# ARS_Schematic.net
KiCad netlist of a schematic drawn in Altium Designer
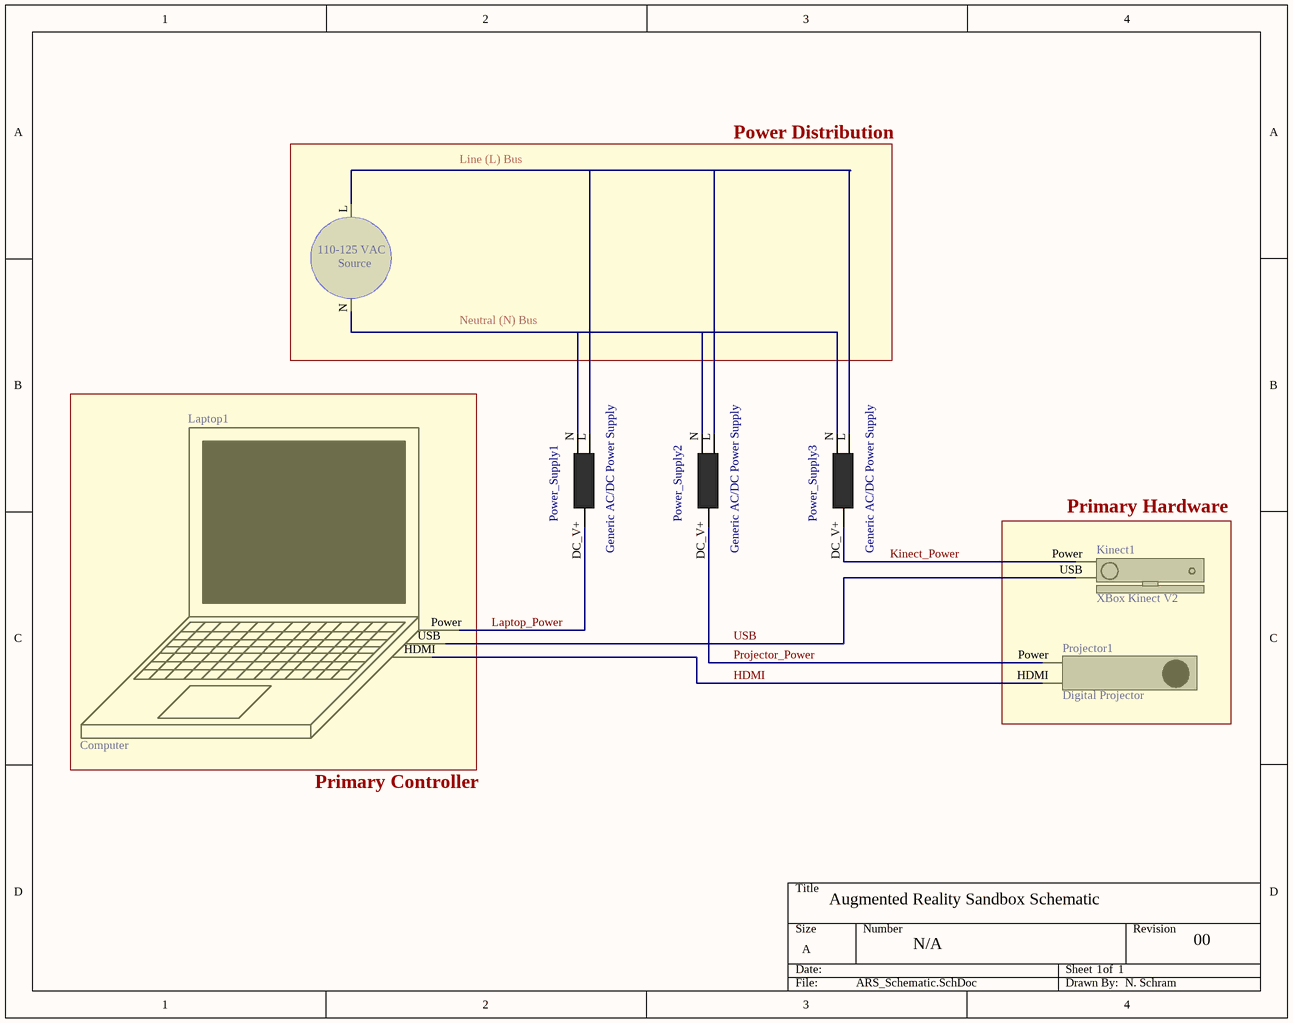
[diagram p0: ARS_Schematic.SchDoc]

(export (version "E")
  (design (tool "Eeschema 10.0.6"))
  (components
    (comp (ref "AC1")
      (value "110-125 VAC")
      (description "110-125 VAC SOURCE")
      (libsource (lib "ARS_Schematic_Library") (part "AC_Power_Source"))
    )
    (comp (ref "Kinect1")
      (value "XBox Kinect V2")
      (description "Microsoft XBox Kinect V2")
      (libsource (lib "ARS_Schematic_Library") (part "Xbox_Kinect_V2"))
    )
    (comp (ref "Laptop1")
      (value "Computer")
      (description "Laptop Computer")
      (libsource (lib "ARS_Schematic_Library") (part "Laptop"))
    )
    (comp (ref "Power_Supply1")
      (value "Generic AC/DC Power Supply")
      (libsource (lib "ARS_Schematic_Library") (part "Generic_Power_Supply"))
    )
    (comp (ref "Power_Supply2")
      (value "Generic AC/DC Power Supply")
      (libsource (lib "ARS_Schematic_Library") (part "Generic_Power_Supply"))
    )
    (comp (ref "Power_Supply3")
      (value "Generic AC/DC Power Supply")
      (libsource (lib "ARS_Schematic_Library") (part "Generic_Power_Supply"))
    )
    (comp (ref "Projector1")
      (value "Digital Projector")
      (description "BenQ Short Throw Digital Projector")
      (libsource (lib "ARS_Schematic_Library") (part "Digital_Projector"))
    )
  )
  (nets
    (net (code "1") (name "/HDMI") (class "Default")
      (node (ref "Laptop1") (pin "HDMI") (pinfunction "HDMI_HDMI") (pintype "passive"))
      (node (ref "Projector1") (pin "HDMI") (pinfunction "HDMI_HDMI") (pintype "passive"))
    )
    (net (code "2") (name "/Kinect_Power") (class "Default")
      (node (ref "Kinect1") (pin "Power") (pinfunction "Power_Power") (pintype "passive"))
      (node (ref "Power_Supply3") (pin "DC_V+") (pinfunction "DC_V+_DC_V+") (pintype "passive"))
    )
    (net (code "3") (name "/Laptop_Power") (class "Default")
      (node (ref "Laptop1") (pin "Power") (pinfunction "Power_Power") (pintype "passive"))
      (node (ref "Power_Supply1") (pin "DC_V+") (pinfunction "DC_V+_DC_V+") (pintype "passive"))
    )
    (net (code "6") (name "/Projector_Power") (class "Default")
      (node (ref "Power_Supply2") (pin "DC_V+") (pinfunction "DC_V+_DC_V+") (pintype "passive"))
      (node (ref "Projector1") (pin "Power") (pinfunction "Power_Power") (pintype "passive"))
    )
    (net (code "7") (name "/USB") (class "Default")
      (node (ref "Kinect1") (pin "USB") (pinfunction "USB_USB") (pintype "passive"))
      (node (ref "Laptop1") (pin "USB") (pinfunction "USB_USB") (pintype "passive"))
    )
    (net (code "8") (name "unconnected-(AC1-PadL)") (class "Default")
      (node (ref "AC1") (pin "L") (pinfunction "L_L") (pintype "passive"))
    )
    (net (code "9") (name "unconnected-(AC1-PadN)") (class "Default")
      (node (ref "AC1") (pin "N") (pinfunction "N_N") (pintype "passive"))
    )
    (net (code "10") (name "unconnected-(Power_Supply1-PadL)") (class "Default")
      (node (ref "Power_Supply1") (pin "L") (pinfunction "L_L") (pintype "passive"))
    )
    (net (code "11") (name "unconnected-(Power_Supply1-PadN)") (class "Default")
      (node (ref "Power_Supply1") (pin "N") (pinfunction "N_N") (pintype "passive"))
    )
    (net (code "12") (name "unconnected-(Power_Supply2-PadL)") (class "Default")
      (node (ref "Power_Supply2") (pin "L") (pinfunction "L_L") (pintype "passive"))
    )
    (net (code "13") (name "unconnected-(Power_Supply2-PadN)") (class "Default")
      (node (ref "Power_Supply2") (pin "N") (pinfunction "N_N") (pintype "passive"))
    )
    (net (code "14") (name "unconnected-(Power_Supply3-PadL)") (class "Default")
      (node (ref "Power_Supply3") (pin "L") (pinfunction "L_L") (pintype "passive"))
    )
    (net (code "15") (name "unconnected-(Power_Supply3-PadN)") (class "Default")
      (node (ref "Power_Supply3") (pin "N") (pinfunction "N_N") (pintype "passive"))
    )
  )
)
